# 05_ElectronicScales.net
KiCad netlist of a schematic drawn in Altium Designer
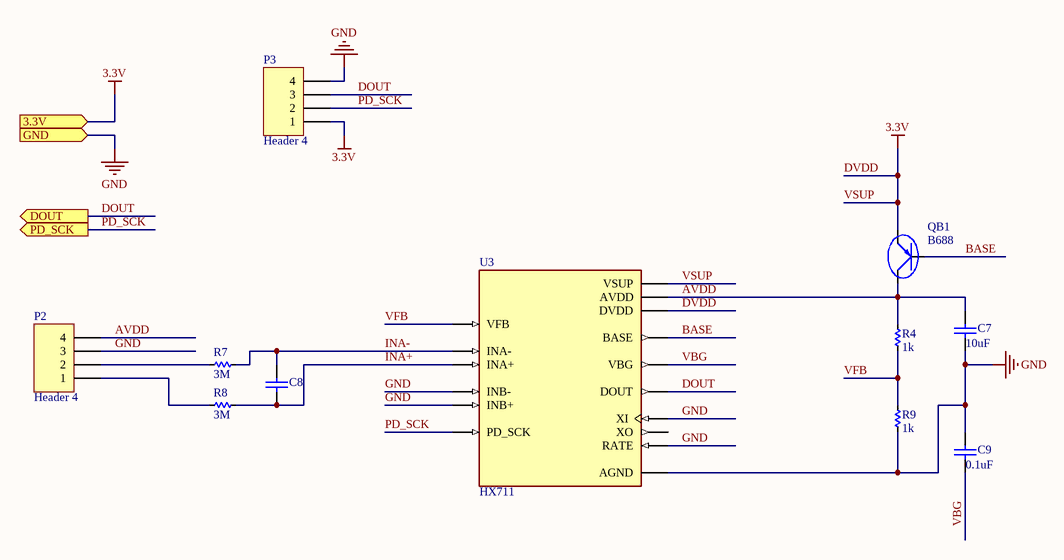
[diagram p0: 05_ElectronicScales.SchDoc]

(export (version "E")
  (design (tool "Eeschema 10.0.6"))
  (components
    (comp (ref "C7")
      (value "10uF")
      (footprint "C0805")
      (description "Capacitor")
      (fields (field (name "PUBLISHER") "Altium Limited"))
      (libsource (lib "My Library") (part "CapSMD"))
    )
    (comp (ref "C8")
      (value "Capacitor Ceramic")
      (footprint "C0805")
      (description "Capacitor")
      (fields (field (name "PUBLISHER") "Altium Limited"))
      (libsource (lib "My Library") (part "CapSMD"))
    )
    (comp (ref "C9")
      (value "0.1uF")
      (footprint "C0805")
      (description "Capacitor")
      (fields (field (name "PUBLISHER") "Altium Limited"))
      (libsource (lib "My Library") (part "CapSMD"))
    )
    (comp (ref "P2")
      (value "Header 4")
      (footprint "HDR1X4")
      (description "Header, 4-Pin")
      (fields (field (name "PUBLISHER") "Altium Limited"))
      (libsource (lib "My Library") (part "Header 4"))
    )
    (comp (ref "P3")
      (value "Header 4")
      (footprint "HDR1X4")
      (description "Header, 4-Pin")
      (fields (field (name "PUBLISHER") "Altium Limited"))
      (libsource (lib "My Library") (part "Header 4"))
    )
    (comp (ref "QB1")
      (value "B688")
      (footprint "QTO-247")
      (description "Transistor Power Supply")
      (libsource (lib "My Library") (part "B688"))
    )
    (comp (ref "R4")
      (value "1k")
      (footprint "RES-SMD-0805")
      (description "Resistor")
      (fields
        (field (name "MANUFACTURER") "Generic Components")
        (field (name "PUBLISHER") "Altium Hobart Technology Centre")
      )
      (libsource (lib "My Library") (part "Res-SMD"))
    )
    (comp (ref "R7")
      (value "3M")
      (footprint "RES-SMD-0805")
      (description "Resistor")
      (fields
        (field (name "MANUFACTURER") "Generic Components")
        (field (name "PUBLISHER") "Altium Hobart Technology Centre")
      )
      (libsource (lib "My Library") (part "Res-SMD"))
    )
    (comp (ref "R8")
      (value "3M")
      (footprint "RES-SMD-0805")
      (description "Resistor")
      (fields
        (field (name "MANUFACTURER") "Generic Components")
        (field (name "PUBLISHER") "Altium Hobart Technology Centre")
      )
      (libsource (lib "My Library") (part "Res-SMD"))
    )
    (comp (ref "R9")
      (value "1k")
      (footprint "RES-SMD-0805")
      (description "Resistor")
      (fields
        (field (name "MANUFACTURER") "Generic Components")
        (field (name "PUBLISHER") "Altium Hobart Technology Centre")
      )
      (libsource (lib "My Library") (part "Res-SMD"))
    )
    (comp (ref "U3")
      (value "HX711")
      (footprint "SOP127P600X180-16N")
      (libsource (lib "HX711") (part "HX711"))
    )
  )
  (nets
    (net (code "1") (name "/AVDD") (class "Default")
      (node (ref "C7") (pin "2") (pinfunction "2_2") (pintype "passive"))
      (node (ref "P2") (pin "4") (pinfunction "4_4") (pintype "passive"))
      (node (ref "QB1") (pin "2") (pinfunction "C_2") (pintype "passive"))
      (node (ref "R4") (pin "1") (pinfunction "1_1") (pintype "passive"))
      (node (ref "U3") (pin "3") (pinfunction "AVDD_3") (pintype "power_in"))
    )
    (net (code "2") (name "/BASE") (class "Default")
      (node (ref "QB1") (pin "1") (pinfunction "B_1") (pintype "passive"))
      (node (ref "U3") (pin "2") (pinfunction "BASE_2") (pintype "output"))
    )
    (net (code "3") (name "/DOUT") (class "Default")
      (node (ref "P3") (pin "3") (pinfunction "3_3") (pintype "passive"))
      (node (ref "U3") (pin "12") (pinfunction "DOUT_12") (pintype "output"))
    )
    (net (code "4") (name "/INA+") (class "Default")
      (node (ref "C8") (pin "1") (pinfunction "1_1") (pintype "passive"))
      (node (ref "R8") (pin "2") (pinfunction "2_2") (pintype "passive"))
      (node (ref "U3") (pin "8") (pinfunction "INA+_8") (pintype "input"))
    )
    (net (code "5") (name "/INA-") (class "Default")
      (node (ref "C8") (pin "2") (pinfunction "2_2") (pintype "passive"))
      (node (ref "R7") (pin "2") (pinfunction "2_2") (pintype "passive"))
      (node (ref "U3") (pin "7") (pinfunction "INA-_7") (pintype "input"))
    )
    (net (code "6") (name "/PD_SCK") (class "Default")
      (node (ref "P3") (pin "2") (pinfunction "2_2") (pintype "passive"))
      (node (ref "U3") (pin "11") (pinfunction "PD_SCK_11") (pintype "input"))
    )
    (net (code "7") (name "/VBG") (class "Default")
      (node (ref "C9") (pin "1") (pinfunction "1_1") (pintype "passive"))
      (node (ref "U3") (pin "6") (pinfunction "VBG_6") (pintype "output"))
    )
    (net (code "8") (name "/VFB") (class "Default")
      (node (ref "R4") (pin "2") (pinfunction "2_2") (pintype "passive"))
      (node (ref "R9") (pin "1") (pinfunction "1_1") (pintype "passive"))
      (node (ref "U3") (pin "4") (pinfunction "VFB_4") (pintype "input"))
    )
    (net (code "9") (name "3.3V") (class "Default")
      (node (ref "P3") (pin "1") (pinfunction "1_1") (pintype "passive"))
      (node (ref "QB1") (pin "3") (pinfunction "E_3") (pintype "passive"))
      (node (ref "U3") (pin "1") (pinfunction "VSUP_1") (pintype "power_in"))
      (node (ref "U3") (pin "16") (pinfunction "DVDD_16") (pintype "power_in"))
    )
    (net (code "10") (name "GND") (class "Default")
      (node (ref "C7") (pin "1") (pinfunction "1_1") (pintype "passive"))
      (node (ref "C9") (pin "2") (pinfunction "2_2") (pintype "passive"))
      (node (ref "P2") (pin "3") (pinfunction "3_3") (pintype "passive"))
      (node (ref "P3") (pin "4") (pinfunction "4_4") (pintype "passive"))
      (node (ref "R9") (pin "2") (pinfunction "2_2") (pintype "passive"))
      (node (ref "U3") (pin "10") (pinfunction "INB+_10") (pintype "input"))
      (node (ref "U3") (pin "14") (pinfunction "XI_14") (pintype "input"))
      (node (ref "U3") (pin "15") (pinfunction "RATE_15") (pintype "input"))
      (node (ref "U3") (pin "5") (pinfunction "AGND_5") (pintype "power_in"))
      (node (ref "U3") (pin "9") (pinfunction "INB-_9") (pintype "input"))
    )
    (net (code "11") (name "Net-(P2-Pad1)") (class "Default")
      (node (ref "P2") (pin "1") (pinfunction "1_1") (pintype "passive"))
      (node (ref "R8") (pin "1") (pinfunction "1_1") (pintype "passive"))
    )
    (net (code "12") (name "Net-(P2-Pad2)") (class "Default")
      (node (ref "P2") (pin "2") (pinfunction "2_2") (pintype "passive"))
      (node (ref "R7") (pin "1") (pinfunction "1_1") (pintype "passive"))
    )
    (net (code "13") (name "unconnected-(U3-XO-Pad13)") (class "Default")
      (node (ref "U3") (pin "13") (pinfunction "XO_13") (pintype "output"))
    )
  )
)
